# Schematic.net
KiCad netlist of a schematic drawn in Altium Designer
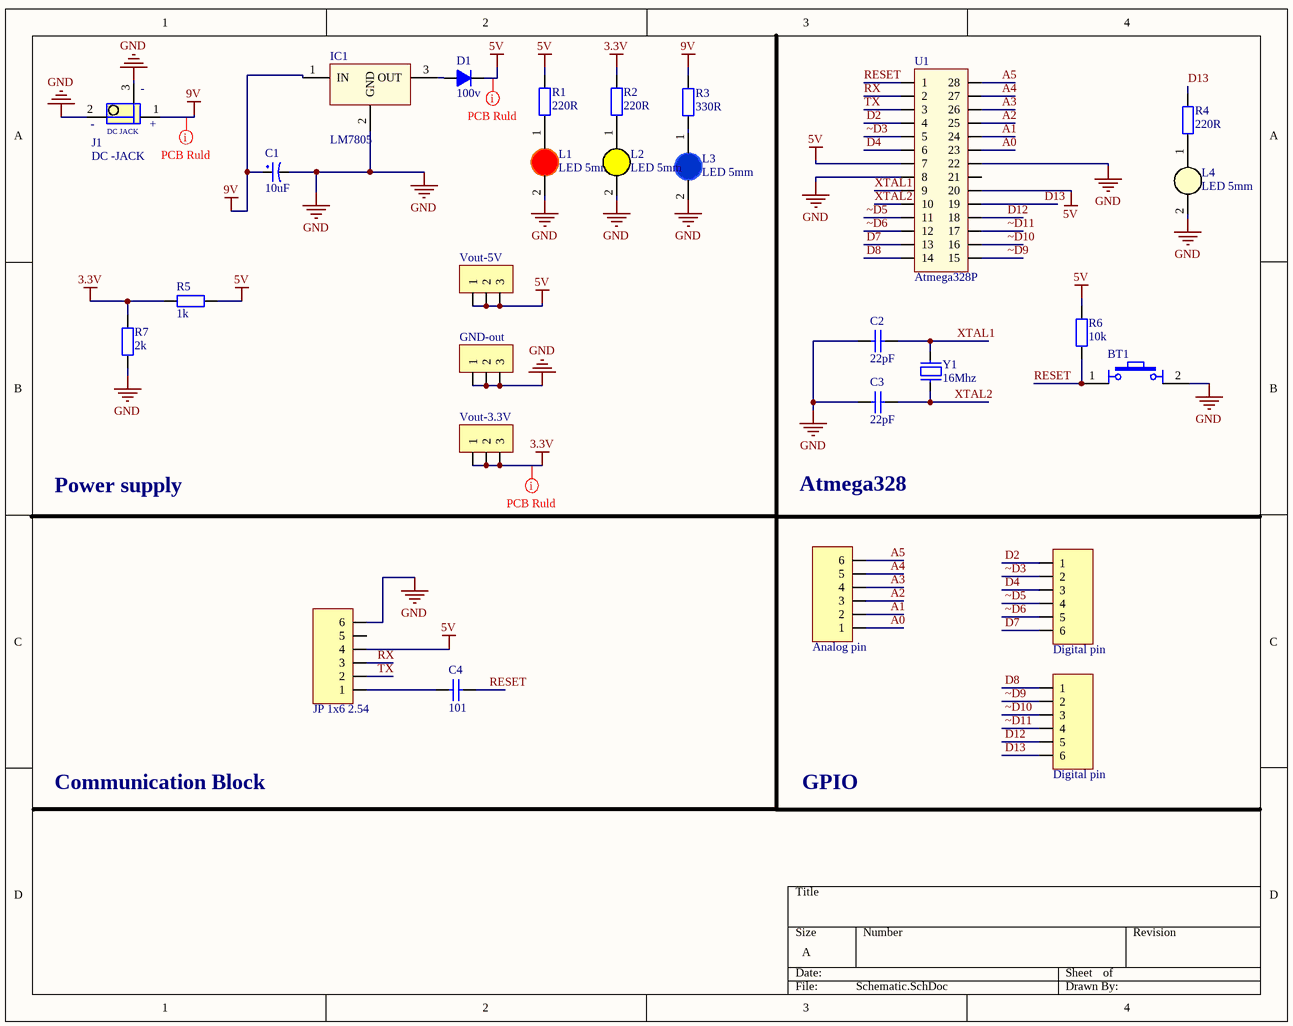
[diagram p0: Schematic.SchDoc]

(export (version "E")
  (design (tool "Eeschema 10.0.6"))
  (components
    (comp (ref "BT1")
      (value "Nut Nhan 4 Chan Cam 6x6")
      (footprint "Nut Nhan 4 Chan Cam 6x6")
      (description "Nut Nhan 4 Chan 6x6mm")
      (libsource (lib "Altium_Lib_by_KhueNguyenCreator") (part "Nut Nhan 4 Chan Cam 6x6"))
    )
    (comp (ref "C1")
      (value "10uF")
      (footprint "tu hoa 4mm")
      (description "Cắm")
      (libsource (lib "Altium_Lib_by_KhueNguyenCreator") (part "Tu Hoa 10uF 25V 4x7"))
    )
    (comp (ref "C2")
      (value "22pF")
      (footprint "tu gom")
      (description "Cắm")
      (libsource (lib "Altium_Lib_by_KhueNguyenCreator") (part "Tu gom 22pF 50V"))
    )
    (comp (ref "C3")
      (value "22pF")
      (footprint "tu gom")
      (description "Cắm")
      (libsource (lib "Altium_Lib_by_KhueNguyenCreator") (part "Tu gom 22pF 50V"))
    )
    (comp (ref "C4")
      (value "101")
      (footprint "tu gom")
      (description "Cắm")
      (libsource (lib "Altium_Lib_by_KhueNguyenCreator") (part "Tu gom 101 50V"))
    )
    (comp (ref "D1")
      (value "100v")
      (footprint "DIODE 1A")
      (description "Cắm")
      (libsource (lib "Altium_Lib_by_KhueNguyenCreator") (part "Diode 1N4007"))
    )
    (comp (ref "GND-out")
      (value "JP 1x3 2.54")
      (footprint "JP 1x3 DT")
      (description "Cắm")
      (libsource (lib "Altium_Lib_by_KhueNguyenCreator") (part "JP 1x3 2.54 Duc Thang"))
    )
    (comp (ref "IC1")
      (value "LM7805")
      (footprint "QTO-220")
      (description "On ap +, from + 5 to + 24VDC")
      (libsource (lib "syhaunguyen") (part "LM78xx"))
    )
    (comp (ref "J1")
      (value "DC -JACK")
      (footprint "CON3_129_PJ-002A_TH_RA")
      (description "3 Pins, 1 Row 228mil Pitch, right angle Connector, male")
      (fields (field (name "MANUFACTURER") "JST") (field (name "MANUFACTURER PART NUMBER") "PJ-002A"))
      (libsource (lib "Altium_Lib_by_KhueNguyenCreator") (part "CON-PLG_3X1-228-DC_JACK"))
    )
    (comp (ref "JP1")
      (value "Digital pin")
      (footprint "JP 1x6 CT")
      (description "Cắm")
      (libsource (lib "") (part "JP 1x6 2.54 Cai Thang_1"))
    )
    (comp (ref "JP2")
      (value "Analog pin")
      (footprint "JP 1x6 CT")
      (description "Cắm")
      (libsource (lib "Altium_Lib_by_KhueNguyenCreator") (part "JP 1x6 2.54 Cai Thang"))
    )
    (comp (ref "JP3")
      (value "JP 1x6 2.54")
      (footprint "JP 1x6 CC")
      (description "Cắm")
      (libsource (lib "Altium_Lib_by_KhueNguyenCreator") (part "JP 1x6 2.54 Cai Cong"))
    )
    (comp (ref "JP4")
      (value "Digital pin")
      (footprint "JP 1x6 CT")
      (description "Cắm")
      (libsource (lib "") (part "JP 1x6 2.54 Cai Thang_1"))
    )
    (comp (ref "L1")
      (value "LED 5mm")
      (footprint "LED-5MM-RED")
      (description "Cắm")
      (libsource (lib "Altium_Lib_by_KhueNguyenCreator") (part "LED 5mm Do"))
    )
    (comp (ref "L2")
      (value "LED 5mm")
      (footprint "LED-5MM-Yellow")
      (description "Cắm")
      (libsource (lib "Altium_Lib_by_KhueNguyenCreator") (part "LED 5mm Vang"))
    )
    (comp (ref "L3")
      (value "LED 5mm")
      (footprint "LED-5MM-BLUE")
      (description "Cắm")
      (libsource (lib "Altium_Lib_by_KhueNguyenCreator") (part "LED 5mm Xanh Duong"))
    )
    (comp (ref "L4")
      (value "LED 5mm")
      (footprint "LED-5MM-WHITE")
      (description "Cắm")
      (libsource (lib "Altium_Lib_by_KhueNguyenCreator") (part "LED 5mm Trang"))
    )
    (comp (ref "R1")
      (value "220R")
      (footprint "tro vach 1/2w")
      (description "Cắm")
      (libsource (lib "Altium_Lib_by_KhueNguyenCreator") (part "Tro Vach 1/2W 5% 240R"))
    )
    (comp (ref "R2")
      (value "220R")
      (footprint "tro vach 1/2w")
      (description "Cắm")
      (libsource (lib "Altium_Lib_by_KhueNguyenCreator") (part "Tro Vach 1/2W 5% 240R"))
    )
    (comp (ref "R3")
      (value "330R")
      (footprint "tro vach 1/2w")
      (description "Cắm")
      (libsource (lib "Altium_Lib_by_KhueNguyenCreator") (part "Tro Vach 1/2W 5% 330R"))
    )
    (comp (ref "R4")
      (value "220R")
      (footprint "tro vach 1/2w")
      (description "Cắm")
      (libsource (lib "Altium_Lib_by_KhueNguyenCreator") (part "Tro Vach 1/2W 5% 240R"))
    )
    (comp (ref "R5")
      (value "1k")
      (footprint "tro vach 1/2w")
      (description "Cắm")
      (libsource (lib "Altium_Lib_by_KhueNguyenCreator") (part "Tro Vach 1/2W 5% 1k"))
    )
    (comp (ref "R6")
      (value "10k")
      (footprint "tro vach 1/2w")
      (description "Cắm")
      (libsource (lib "Altium_Lib_by_KhueNguyenCreator") (part "Tro Vach 1/2W 5% 10k"))
    )
    (comp (ref "R7")
      (value "2k")
      (footprint "tro vach 1/4w")
      (description "Cắm")
      (libsource (lib "Altium_Lib_by_KhueNguyenCreator") (part "Tro Vach 1/4W 5% 2k"))
    )
    (comp (ref "U1")
      (value "Atmega328P")
      (footprint "DIP28/W0.3")
      (description "DIP28")
      (libsource (lib "syhaunguyen") (part "DIP28"))
    )
    (comp (ref "Vout-3.3V")
      (value "JP 1x3 2.54")
      (footprint "JP 1x3 DT")
      (description "Cắm")
      (libsource (lib "Altium_Lib_by_KhueNguyenCreator") (part "JP 1x3 2.54 Duc Thang"))
    )
    (comp (ref "Vout-5V")
      (value "JP 1x3 2.54")
      (footprint "JP 1x3 DT")
      (description "Cắm")
      (libsource (lib "Altium_Lib_by_KhueNguyenCreator") (part "JP 1x3 2.54 Duc Thang"))
    )
    (comp (ref "Y1")
      (value "16Mhz")
      (footprint "Thach Anh 2 chan cam")
      (description "Crystal For all Crystal 2pin.")
      (libsource (lib "Altium_Lib_by_KhueNguyenCreator") (part "Thach Anh 2 chan Cam"))
    )
  )
  (nets
    (net (code "1") (name "/A0") (class "Default")
      (node (ref "JP2") (pin "1") (pinfunction "1_1") (pintype "passive"))
      (node (ref "U1") (pin "23") (pinfunction "23_23") (pintype "passive"))
    )
    (net (code "2") (name "/A1") (class "Default")
      (node (ref "JP2") (pin "2") (pinfunction "2_2") (pintype "passive"))
      (node (ref "U1") (pin "24") (pinfunction "24_24") (pintype "passive"))
    )
    (net (code "3") (name "/A2") (class "Default")
      (node (ref "JP2") (pin "3") (pinfunction "3_3") (pintype "passive"))
      (node (ref "U1") (pin "25") (pinfunction "25_25") (pintype "passive"))
    )
    (net (code "4") (name "/A3") (class "Default")
      (node (ref "JP2") (pin "4") (pinfunction "4_4") (pintype "passive"))
      (node (ref "U1") (pin "26") (pinfunction "26_26") (pintype "passive"))
    )
    (net (code "5") (name "/A4") (class "Default")
      (node (ref "JP2") (pin "5") (pinfunction "5_5") (pintype "passive"))
      (node (ref "U1") (pin "27") (pinfunction "27_27") (pintype "passive"))
    )
    (net (code "6") (name "/A5") (class "Default")
      (node (ref "JP2") (pin "6") (pinfunction "6_6") (pintype "passive"))
      (node (ref "U1") (pin "28") (pinfunction "28_28") (pintype "passive"))
    )
    (net (code "7") (name "/D2") (class "Default")
      (node (ref "JP1") (pin "1") (pinfunction "1_1") (pintype "passive"))
      (node (ref "U1") (pin "4") (pinfunction "4_4") (pintype "passive"))
    )
    (net (code "8") (name "/D4") (class "Default")
      (node (ref "JP1") (pin "3") (pinfunction "3_3") (pintype "passive"))
      (node (ref "U1") (pin "6") (pinfunction "6_6") (pintype "passive"))
    )
    (net (code "9") (name "/D7") (class "Default")
      (node (ref "JP1") (pin "6") (pinfunction "6_6") (pintype "passive"))
      (node (ref "U1") (pin "13") (pinfunction "13_13") (pintype "passive"))
    )
    (net (code "10") (name "/D8") (class "Default")
      (node (ref "JP4") (pin "1") (pinfunction "1_1") (pintype "passive"))
      (node (ref "U1") (pin "14") (pinfunction "14_14") (pintype "passive"))
    )
    (net (code "11") (name "/D12") (class "Default")
      (node (ref "JP4") (pin "5") (pinfunction "5_5") (pintype "passive"))
      (node (ref "U1") (pin "18") (pinfunction "18_18") (pintype "passive"))
    )
    (net (code "12") (name "/D13") (class "Default")
      (node (ref "JP4") (pin "6") (pinfunction "6_6") (pintype "passive"))
      (node (ref "R4") (pin "2") (pinfunction "2_2") (pintype "passive"))
      (node (ref "U1") (pin "19") (pinfunction "19_19") (pintype "passive"))
    )
    (net (code "13") (name "/RESET") (class "Default")
      (node (ref "BT1") (pin "1") (pintype "passive"))
      (node (ref "C4") (pin "1") (pinfunction "1_1") (pintype "passive"))
      (node (ref "R6") (pin "1") (pinfunction "1_1") (pintype "passive"))
      (node (ref "U1") (pin "1") (pinfunction "1_1") (pintype "passive"))
    )
    (net (code "14") (name "/RX") (class "Default")
      (node (ref "JP3") (pin "3") (pinfunction "3_3") (pintype "passive"))
      (node (ref "U1") (pin "2") (pinfunction "2_2") (pintype "passive"))
    )
    (net (code "15") (name "/TX") (class "Default")
      (node (ref "JP3") (pin "2") (pinfunction "2_2") (pintype "passive"))
      (node (ref "U1") (pin "3") (pinfunction "3_3") (pintype "passive"))
    )
    (net (code "16") (name "/XTAL1") (class "Default")
      (node (ref "C2") (pin "1") (pinfunction "1_1") (pintype "passive"))
      (node (ref "U1") (pin "9") (pinfunction "9_9") (pintype "passive"))
      (node (ref "Y1") (pin "2") (pinfunction "2_2") (pintype "passive"))
    )
    (net (code "17") (name "/XTAL2") (class "Default")
      (node (ref "C3") (pin "1") (pinfunction "1_1") (pintype "passive"))
      (node (ref "U1") (pin "10") (pinfunction "10_10") (pintype "passive"))
      (node (ref "Y1") (pin "1") (pinfunction "1_1") (pintype "passive"))
    )
    (net (code "18") (name "/~D3") (class "Default")
      (node (ref "JP1") (pin "2") (pinfunction "2_2") (pintype "passive"))
      (node (ref "U1") (pin "5") (pinfunction "5_5") (pintype "passive"))
    )
    (net (code "19") (name "/~D5") (class "Default")
      (node (ref "JP1") (pin "4") (pinfunction "4_4") (pintype "passive"))
      (node (ref "U1") (pin "11") (pinfunction "11_11") (pintype "passive"))
    )
    (net (code "20") (name "/~D6") (class "Default")
      (node (ref "JP1") (pin "5") (pinfunction "5_5") (pintype "passive"))
      (node (ref "U1") (pin "12") (pinfunction "12_12") (pintype "passive"))
    )
    (net (code "21") (name "/~D9") (class "Default")
      (node (ref "JP4") (pin "2") (pinfunction "2_2") (pintype "passive"))
      (node (ref "U1") (pin "15") (pinfunction "15_15") (pintype "passive"))
    )
    (net (code "22") (name "/~D10") (class "Default")
      (node (ref "JP4") (pin "3") (pinfunction "3_3") (pintype "passive"))
      (node (ref "U1") (pin "16") (pinfunction "16_16") (pintype "passive"))
    )
    (net (code "23") (name "/~D11") (class "Default")
      (node (ref "JP4") (pin "4") (pinfunction "4_4") (pintype "passive"))
      (node (ref "U1") (pin "17") (pinfunction "17_17") (pintype "passive"))
    )
    (net (code "24") (name "3.3V") (class "Default")
      (node (ref "R2") (pin "2") (pinfunction "2_2") (pintype "passive"))
      (node (ref "R5") (pin "1") (pinfunction "1_1") (pintype "passive"))
      (node (ref "R7") (pin "2") (pinfunction "2_2") (pintype "passive"))
      (node (ref "Vout-3.3V") (pin "1") (pinfunction "1_1") (pintype "passive"))
      (node (ref "Vout-3.3V") (pin "2") (pinfunction "2_2") (pintype "passive"))
      (node (ref "Vout-3.3V") (pin "3") (pinfunction "3_3") (pintype "passive"))
    )
    (net (code "25") (name "5V") (class "Default")
      (node (ref "D1") (pin "2") (pinfunction "K_2") (pintype "passive"))
      (node (ref "JP3") (pin "4") (pinfunction "4_4") (pintype "passive"))
      (node (ref "R1") (pin "2") (pinfunction "2_2") (pintype "passive"))
      (node (ref "R5") (pin "2") (pinfunction "2_2") (pintype "passive"))
      (node (ref "R6") (pin "2") (pinfunction "2_2") (pintype "passive"))
      (node (ref "U1") (pin "20") (pinfunction "20_20") (pintype "passive"))
      (node (ref "U1") (pin "7") (pinfunction "7_7") (pintype "passive"))
      (node (ref "Vout-5V") (pin "1") (pinfunction "1_1") (pintype "passive"))
      (node (ref "Vout-5V") (pin "2") (pinfunction "2_2") (pintype "passive"))
      (node (ref "Vout-5V") (pin "3") (pinfunction "3_3") (pintype "passive"))
    )
    (net (code "26") (name "9V") (class "Default")
      (node (ref "C1") (pin "1") (pinfunction "1_1") (pintype "passive"))
      (node (ref "IC1") (pin "1") (pinfunction "IN_1") (pintype "passive"))
      (node (ref "J1") (pin "1") (pinfunction "1_1") (pintype "passive"))
      (node (ref "R3") (pin "2") (pinfunction "2_2") (pintype "passive"))
    )
    (net (code "27") (name "GND") (class "Default")
      (node (ref "BT1") (pin "2") (pintype "passive"))
      (node (ref "C1") (pin "2") (pinfunction "2_2") (pintype "passive"))
      (node (ref "C2") (pin "2") (pinfunction "2_2") (pintype "passive"))
      (node (ref "C3") (pin "2") (pinfunction "2_2") (pintype "passive"))
      (node (ref "GND-out") (pin "1") (pinfunction "1_1") (pintype "passive"))
      (node (ref "GND-out") (pin "2") (pinfunction "2_2") (pintype "passive"))
      (node (ref "GND-out") (pin "3") (pinfunction "3_3") (pintype "passive"))
      (node (ref "IC1") (pin "2") (pinfunction "GND_2") (pintype "passive"))
      (node (ref "J1") (pin "2") (pinfunction "2_2") (pintype "passive"))
      (node (ref "J1") (pin "3") (pinfunction "-_3") (pintype "passive"))
      (node (ref "JP3") (pin "6") (pinfunction "6_6") (pintype "passive"))
      (node (ref "L1") (pin "2") (pinfunction "K_2") (pintype "passive"))
      (node (ref "L2") (pin "2") (pinfunction "K_2") (pintype "passive"))
      (node (ref "L3") (pin "2") (pinfunction "K_2") (pintype "passive"))
      (node (ref "L4") (pin "2") (pinfunction "K_2") (pintype "passive"))
      (node (ref "R7") (pin "1") (pinfunction "1_1") (pintype "passive"))
      (node (ref "U1") (pin "22") (pinfunction "22_22") (pintype "passive"))
      (node (ref "U1") (pin "8") (pinfunction "8_8") (pintype "passive"))
    )
    (net (code "28") (name "Net-(C4-Pad2)") (class "Default")
      (node (ref "C4") (pin "2") (pinfunction "2_2") (pintype "passive"))
      (node (ref "JP3") (pin "1") (pinfunction "1_1") (pintype "passive"))
    )
    (net (code "29") (name "Net-(D1-A)") (class "Default")
      (node (ref "D1") (pin "1") (pinfunction "A_1") (pintype "passive"))
      (node (ref "IC1") (pin "3") (pinfunction "OUT_3") (pintype "passive"))
    )
    (net (code "30") (name "Net-(L1-A)") (class "Default")
      (node (ref "L1") (pin "1") (pinfunction "A_1") (pintype "passive"))
      (node (ref "R1") (pin "1") (pinfunction "1_1") (pintype "passive"))
    )
    (net (code "31") (name "Net-(L2-A)") (class "Default")
      (node (ref "L2") (pin "1") (pinfunction "A_1") (pintype "passive"))
      (node (ref "R2") (pin "1") (pinfunction "1_1") (pintype "passive"))
    )
    (net (code "32") (name "Net-(L3-A)") (class "Default")
      (node (ref "L3") (pin "1") (pinfunction "A_1") (pintype "passive"))
      (node (ref "R3") (pin "1") (pinfunction "1_1") (pintype "passive"))
    )
    (net (code "33") (name "Net-(L4-A)") (class "Default")
      (node (ref "L4") (pin "1") (pinfunction "A_1") (pintype "passive"))
      (node (ref "R4") (pin "1") (pinfunction "1_1") (pintype "passive"))
    )
    (net (code "34") (name "unconnected-(JP3-Pad5)") (class "Default")
      (node (ref "JP3") (pin "5") (pinfunction "5_5") (pintype "passive"))
    )
    (net (code "35") (name "unconnected-(U1-Pad21)") (class "Default")
      (node (ref "U1") (pin "21") (pinfunction "21_21") (pintype "passive"))
    )
  )
)
